# P1_Alim.net
KiCad netlist of a schematic drawn in Altium Designer
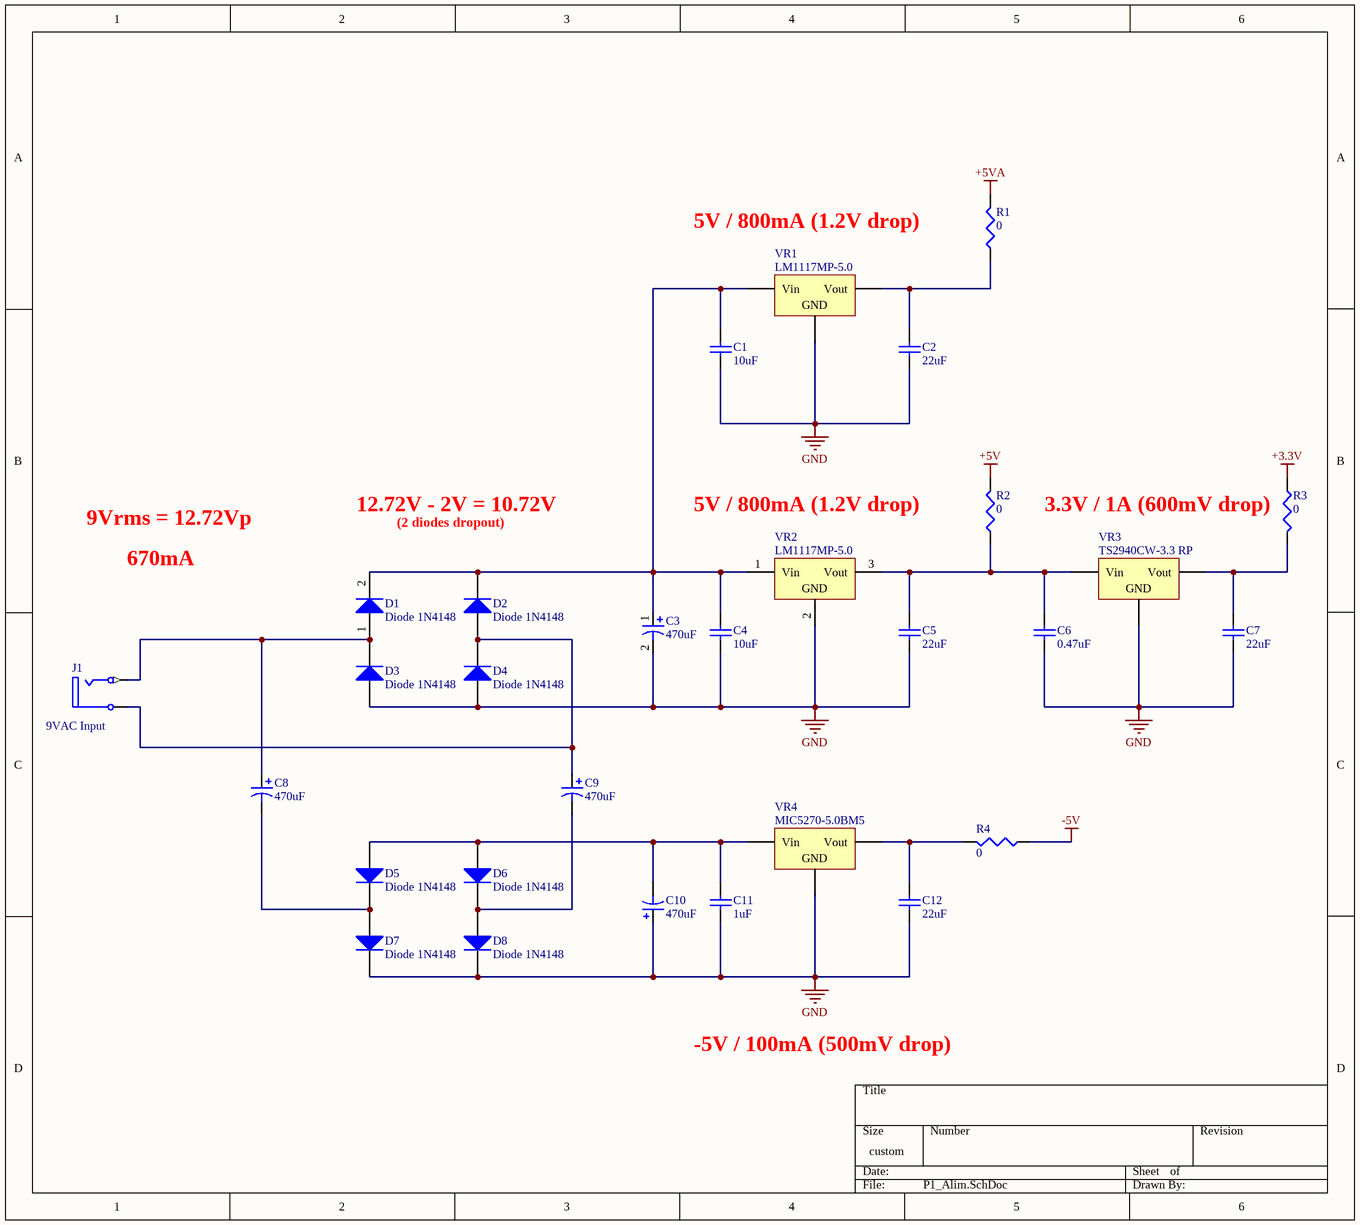
[diagram p0: P1_Alim.SchDoc]

(export (version "E")
  (design (tool "Eeschema 10.0.6"))
  (components
    (comp (ref "C1")
      (value "10uF")
      (footprint "CAP 0603 (1608 metric)")
      (description "Capacitor (Semiconductor SIM Model)")
      (libsource (lib "Miscellaneous Devices") (part "Cap Semi"))
    )
    (comp (ref "C2")
      (value "22uF")
      (footprint "CAP 0603 (1608 metric)")
      (description "Capacitor (Semiconductor SIM Model)")
      (libsource (lib "Miscellaneous Devices") (part "Cap Semi"))
    )
    (comp (ref "C3")
      (value "470uF")
      (footprint "Condo Electro 5mm")
      (description "Polarized Capacitor (Radial)")
      (libsource (lib "") (part "Cap Pol1_1"))
    )
    (comp (ref "C4")
      (value "10uF")
      (footprint "CAP 0603 (1608 metric)")
      (description "Capacitor (Semiconductor SIM Model)")
      (libsource (lib "Miscellaneous Devices") (part "Cap Semi"))
    )
    (comp (ref "C5")
      (value "22uF")
      (footprint "CAP 0603 (1608 metric)")
      (description "Capacitor (Semiconductor SIM Model)")
      (libsource (lib "Miscellaneous Devices") (part "Cap Semi"))
    )
    (comp (ref "C6")
      (value "0.47uF")
      (footprint "CAP 0603 (1608 metric)")
      (description "Capacitor (Semiconductor SIM Model)")
      (libsource (lib "Miscellaneous Devices") (part "Cap Semi"))
    )
    (comp (ref "C7")
      (value "22uF")
      (footprint "CAP 0603 (1608 metric)")
      (description "Capacitor (Semiconductor SIM Model)")
      (libsource (lib "Miscellaneous Devices") (part "Cap Semi"))
    )
    (comp (ref "C8")
      (value "470uF")
      (footprint "Condo Electro 5mm")
      (description "Polarized Capacitor (Radial)")
      (libsource (lib "Miscellaneous Devices") (part "Cap Pol1"))
    )
    (comp (ref "C9")
      (value "470uF")
      (footprint "Condo Electro 5mm")
      (description "Polarized Capacitor (Radial)")
      (libsource (lib "Miscellaneous Devices") (part "Cap Pol1"))
    )
    (comp (ref "C10")
      (value "470uF")
      (footprint "Condo Electro 5mm")
      (description "Polarized Capacitor (Radial)")
      (libsource (lib "Miscellaneous Devices") (part "Cap Pol1"))
    )
    (comp (ref "C11")
      (value "1uF")
      (footprint "CAP 0603 (1608 metric)")
      (description "Capacitor (Semiconductor SIM Model)")
      (libsource (lib "Miscellaneous Devices") (part "Cap Semi"))
    )
    (comp (ref "C12")
      (value "22uF")
      (footprint "CAP 0603 (1608 metric)")
      (description "Capacitor (Semiconductor SIM Model)")
      (libsource (lib "Miscellaneous Devices") (part "Cap Semi"))
    )
    (comp (ref "D1")
      (value "Diode 1N4148")
      (footprint "1N4148")
      (description "High Conductance Fast Diode")
      (libsource (lib "") (part "Diode 1N4148_1"))
    )
    (comp (ref "D2")
      (value "Diode 1N4148")
      (footprint "1N4148")
      (description "High Conductance Fast Diode")
      (libsource (lib "Miscellaneous Devices") (part "Diode 1N4148"))
    )
    (comp (ref "D3")
      (value "Diode 1N4148")
      (footprint "1N4148")
      (description "High Conductance Fast Diode")
      (libsource (lib "Miscellaneous Devices") (part "Diode 1N4148"))
    )
    (comp (ref "D4")
      (value "Diode 1N4148")
      (footprint "1N4148")
      (description "High Conductance Fast Diode")
      (libsource (lib "Miscellaneous Devices") (part "Diode 1N4148"))
    )
    (comp (ref "D5")
      (value "Diode 1N4148")
      (footprint "1N4148")
      (description "High Conductance Fast Diode")
      (libsource (lib "Miscellaneous Devices") (part "Diode 1N4148"))
    )
    (comp (ref "D6")
      (value "Diode 1N4148")
      (footprint "1N4148")
      (description "High Conductance Fast Diode")
      (libsource (lib "Miscellaneous Devices") (part "Diode 1N4148"))
    )
    (comp (ref "D7")
      (value "Diode 1N4148")
      (footprint "1N4148")
      (description "High Conductance Fast Diode")
      (libsource (lib "Miscellaneous Devices") (part "Diode 1N4148"))
    )
    (comp (ref "D8")
      (value "Diode 1N4148")
      (footprint "1N4148")
      (description "High Conductance Fast Diode")
      (libsource (lib "Miscellaneous Devices") (part "Diode 1N4148"))
    )
    (comp (ref "J1")
      (value "9VAC Input")
      (description "Jack Socket, 1/4\" [6.5mm], Thru-Hole, Vertical, 2-Conductor Open Circuit")
      (libsource (lib "Miscellaneous Connectors") (part "Phonejack2"))
    )
    (comp (ref "R1")
      (value "0")
      (footprint "RES 0603 (1608 metric)")
      (description "Resistor")
      (libsource (lib "Miscellaneous Devices") (part "Res3"))
    )
    (comp (ref "R2")
      (value "0")
      (footprint "RES 0603 (1608 metric)")
      (description "Resistor")
      (libsource (lib "Miscellaneous Devices") (part "Res3"))
    )
    (comp (ref "R3")
      (value "0")
      (footprint "RES 0603 (1608 metric)")
      (description "Resistor")
      (libsource (lib "Miscellaneous Devices") (part "Res3"))
    )
    (comp (ref "R4")
      (value "0")
      (footprint "RES 0603 (1608 metric)")
      (description "Resistor")
      (libsource (lib "Miscellaneous Devices") (part "Res3"))
    )
    (comp (ref "VR1")
      (value "LM1117MP-5.0")
      (footprint "SOT-223")
      (description "Voltage Regulator")
      (libsource (lib "Miscellaneous Devices") (part "Volt Reg"))
    )
    (comp (ref "VR2")
      (value "LM1117MP-5.0")
      (footprint "SOT-223")
      (description "Voltage Regulator")
      (libsource (lib "") (part "Volt Reg_1"))
    )
    (comp (ref "VR3")
      (value "TS2940CW-3.3 RP")
      (footprint "SOT-223")
      (description "Voltage Regulator")
      (libsource (lib "Miscellaneous Devices") (part "Volt Reg"))
    )
    (comp (ref "VR4")
      (value "MIC5270-5.0BM5")
      (description "Voltage Regulator")
      (libsource (lib "Miscellaneous Devices") (part "Volt Reg"))
    )
  )
  (nets
    (net (code "1") (name "+3.3V") (class "Default")
      (node (ref "R3") (pin "1") (pinfunction "1_1") (pintype "passive"))
    )
    (net (code "2") (name "+5V") (class "Default")
      (node (ref "R2") (pin "2") (pinfunction "2_2") (pintype "passive"))
    )
    (net (code "3") (name "+5VA") (class "Default")
      (node (ref "R1") (pin "2") (pinfunction "2_2") (pintype "passive"))
    )
    (net (code "4") (name "-5V") (class "Default")
      (node (ref "R4") (pin "1") (pinfunction "1_1") (pintype "passive"))
    )
    (net (code "5") (name "GND") (class "Default")
      (node (ref "C1") (pin "1") (pinfunction "1_1") (pintype "passive"))
      (node (ref "C10") (pin "1") (pinfunction "1_1") (pintype "passive"))
      (node (ref "C11") (pin "1") (pinfunction "1_1") (pintype "passive"))
      (node (ref "C12") (pin "1") (pinfunction "1_1") (pintype "passive"))
      (node (ref "C2") (pin "1") (pinfunction "1_1") (pintype "passive"))
      (node (ref "C3") (pin "2") (pinfunction "2_2") (pintype "passive"))
      (node (ref "C4") (pin "1") (pinfunction "1_1") (pintype "passive"))
      (node (ref "C5") (pin "1") (pinfunction "1_1") (pintype "passive"))
      (node (ref "C6") (pin "1") (pinfunction "1_1") (pintype "passive"))
      (node (ref "C7") (pin "1") (pinfunction "1_1") (pintype "passive"))
      (node (ref "D3") (pin "1") (pinfunction "A_1") (pintype "passive"))
      (node (ref "D4") (pin "1") (pinfunction "A_1") (pintype "passive"))
      (node (ref "D7") (pin "2") (pinfunction "K_2") (pintype "passive"))
      (node (ref "D8") (pin "2") (pinfunction "K_2") (pintype "passive"))
      (node (ref "VR1") (pin "2") (pinfunction "GND_2") (pintype "passive"))
      (node (ref "VR2") (pin "2") (pinfunction "GND_2") (pintype "passive"))
      (node (ref "VR3") (pin "2") (pinfunction "GND_2") (pintype "passive"))
      (node (ref "VR4") (pin "2") (pinfunction "GND_2") (pintype "passive"))
    )
    (net (code "6") (name "Net-(D1-A)") (class "Default")
      (node (ref "C8") (pin "1") (pinfunction "1_1") (pintype "passive"))
      (node (ref "D1") (pin "1") (pinfunction "A_1") (pintype "passive"))
      (node (ref "D3") (pin "2") (pinfunction "K_2") (pintype "passive"))
      (node (ref "J1") (pin "1") (pinfunction "T_1") (pintype "output"))
    )
    (net (code "7") (name "Net-(D1-K)") (class "Default")
      (node (ref "C1") (pin "2") (pinfunction "2_2") (pintype "passive"))
      (node (ref "C3") (pin "1") (pinfunction "1_1") (pintype "passive"))
      (node (ref "C4") (pin "2") (pinfunction "2_2") (pintype "passive"))
      (node (ref "D1") (pin "2") (pinfunction "K_2") (pintype "passive"))
      (node (ref "D2") (pin "2") (pinfunction "K_2") (pintype "passive"))
      (node (ref "VR1") (pin "1") (pinfunction "Vin_1") (pintype "passive"))
      (node (ref "VR2") (pin "1") (pinfunction "Vin_1") (pintype "passive"))
    )
    (net (code "8") (name "Net-(D2-A)") (class "Default")
      (node (ref "C9") (pin "1") (pinfunction "1_1") (pintype "passive"))
      (node (ref "D2") (pin "1") (pinfunction "A_1") (pintype "passive"))
      (node (ref "D4") (pin "2") (pinfunction "K_2") (pintype "passive"))
      (node (ref "J1") (pin "5") (pinfunction "S_5") (pintype "power_in"))
    )
    (net (code "9") (name "Net-(D5-A)") (class "Default")
      (node (ref "C10") (pin "2") (pinfunction "2_2") (pintype "passive"))
      (node (ref "C11") (pin "2") (pinfunction "2_2") (pintype "passive"))
      (node (ref "D5") (pin "1") (pinfunction "A_1") (pintype "passive"))
      (node (ref "D6") (pin "1") (pinfunction "A_1") (pintype "passive"))
      (node (ref "VR4") (pin "1") (pinfunction "Vin_1") (pintype "passive"))
    )
    (net (code "10") (name "Net-(D5-K)") (class "Default")
      (node (ref "C8") (pin "2") (pinfunction "2_2") (pintype "passive"))
      (node (ref "D5") (pin "2") (pinfunction "K_2") (pintype "passive"))
      (node (ref "D7") (pin "1") (pinfunction "A_1") (pintype "passive"))
    )
    (net (code "11") (name "Net-(D6-K)") (class "Default")
      (node (ref "C9") (pin "2") (pinfunction "2_2") (pintype "passive"))
      (node (ref "D6") (pin "2") (pinfunction "K_2") (pintype "passive"))
      (node (ref "D8") (pin "1") (pinfunction "A_1") (pintype "passive"))
    )
    (net (code "12") (name "Net-(VR1-Vout)") (class "Default")
      (node (ref "C2") (pin "2") (pinfunction "2_2") (pintype "passive"))
      (node (ref "R1") (pin "1") (pinfunction "1_1") (pintype "passive"))
      (node (ref "VR1") (pin "3") (pinfunction "Vout_3") (pintype "passive"))
    )
    (net (code "13") (name "Net-(VR2-Vout)") (class "Default")
      (node (ref "C5") (pin "2") (pinfunction "2_2") (pintype "passive"))
      (node (ref "C6") (pin "2") (pinfunction "2_2") (pintype "passive"))
      (node (ref "R2") (pin "1") (pinfunction "1_1") (pintype "passive"))
      (node (ref "VR2") (pin "3") (pinfunction "Vout_3") (pintype "passive"))
      (node (ref "VR3") (pin "1") (pinfunction "Vin_1") (pintype "passive"))
    )
    (net (code "14") (name "Net-(VR3-Vout)") (class "Default")
      (node (ref "C7") (pin "2") (pinfunction "2_2") (pintype "passive"))
      (node (ref "R3") (pin "2") (pinfunction "2_2") (pintype "passive"))
      (node (ref "VR3") (pin "3") (pinfunction "Vout_3") (pintype "passive"))
    )
    (net (code "15") (name "Net-(VR4-Vout)") (class "Default")
      (node (ref "C12") (pin "2") (pinfunction "2_2") (pintype "passive"))
      (node (ref "R4") (pin "2") (pinfunction "2_2") (pintype "passive"))
      (node (ref "VR4") (pin "3") (pinfunction "Vout_3") (pintype "passive"))
    )
  )
)
